# Headers.net
KiCad netlist of a schematic drawn in Altium Designer
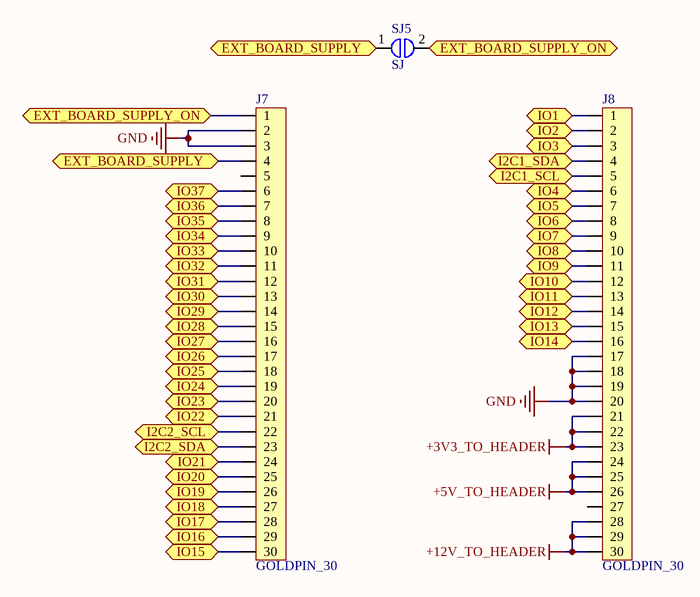
[diagram p0: Headers.SchDoc]

(export (version "E")
  (design (tool "Eeschema 10.0.6"))
  (components
    (comp (ref "J7")
      (value "GOLDPIN_30")
      (footprint "PIN_HEADER_30_MALE")
      (libsource (lib "przem_lib") (part "GOLDPIN_30"))
    )
    (comp (ref "J8")
      (value "GOLDPIN_30")
      (footprint "PIN_HEADER_30_MALE")
      (libsource (lib "przem_lib") (part "GOLDPIN_30"))
    )
    (comp (ref "SJ5") (value "SJ") (footprint "SJ") (libsource (lib "przem_lib") (part "SJ")))
  )
  (nets
    (net (code "1") (name "+3V3_TO_HEADER") (class "Default")
      (node (ref "J8") (pin "21") (pinfunction "21_21") (pintype "passive"))
      (node (ref "J8") (pin "22") (pinfunction "22_22") (pintype "passive"))
      (node (ref "J8") (pin "23") (pinfunction "23_23") (pintype "passive"))
    )
    (net (code "2") (name "+5V_TO_HEADER") (class "Default")
      (node (ref "J8") (pin "24") (pinfunction "24_24") (pintype "passive"))
      (node (ref "J8") (pin "25") (pinfunction "25_25") (pintype "passive"))
      (node (ref "J8") (pin "26") (pinfunction "26_26") (pintype "passive"))
    )
    (net (code "3") (name "+12V_TO_HEADER") (class "Default")
      (node (ref "J8") (pin "28") (pinfunction "28_28") (pintype "passive"))
      (node (ref "J8") (pin "29") (pinfunction "29_29") (pintype "passive"))
      (node (ref "J8") (pin "30") (pinfunction "30_30") (pintype "passive"))
    )
    (net (code "4") (name "/EXT_BOARD_SUPPLY") (class "Default")
      (node (ref "J7") (pin "4") (pinfunction "4_4") (pintype "passive"))
      (node (ref "SJ5") (pin "1") (pinfunction "1_1") (pintype "passive"))
    )
    (net (code "5") (name "/EXT_BOARD_SUPPLY_ON") (class "Default")
      (node (ref "J7") (pin "1") (pinfunction "1_1") (pintype "passive"))
      (node (ref "SJ5") (pin "2") (pinfunction "2_2") (pintype "passive"))
    )
    (net (code "6") (name "/I2C1_SCL") (class "Default")
      (node (ref "J8") (pin "5") (pinfunction "5_5") (pintype "passive"))
    )
    (net (code "7") (name "/I2C1_SDA") (class "Default")
      (node (ref "J8") (pin "4") (pinfunction "4_4") (pintype "passive"))
    )
    (net (code "8") (name "/I2C2_SCL") (class "Default")
      (node (ref "J7") (pin "22") (pinfunction "22_22") (pintype "passive"))
    )
    (net (code "9") (name "/I2C2_SDA") (class "Default")
      (node (ref "J7") (pin "23") (pinfunction "23_23") (pintype "passive"))
    )
    (net (code "10") (name "/IO1") (class "Default")
      (node (ref "J8") (pin "1") (pinfunction "1_1") (pintype "passive"))
    )
    (net (code "11") (name "/IO2") (class "Default")
      (node (ref "J8") (pin "2") (pinfunction "2_2") (pintype "passive"))
    )
    (net (code "12") (name "/IO3") (class "Default")
      (node (ref "J8") (pin "3") (pinfunction "3_3") (pintype "passive"))
    )
    (net (code "13") (name "/IO4") (class "Default")
      (node (ref "J8") (pin "6") (pinfunction "6_6") (pintype "passive"))
    )
    (net (code "14") (name "/IO5") (class "Default")
      (node (ref "J8") (pin "7") (pinfunction "7_7") (pintype "passive"))
    )
    (net (code "15") (name "/IO6") (class "Default")
      (node (ref "J8") (pin "8") (pinfunction "8_8") (pintype "passive"))
    )
    (net (code "16") (name "/IO7") (class "Default")
      (node (ref "J8") (pin "9") (pinfunction "9_9") (pintype "passive"))
    )
    (net (code "17") (name "/IO8") (class "Default")
      (node (ref "J8") (pin "10") (pinfunction "10_10") (pintype "passive"))
    )
    (net (code "18") (name "/IO9") (class "Default")
      (node (ref "J8") (pin "11") (pinfunction "11_11") (pintype "passive"))
    )
    (net (code "19") (name "/IO10") (class "Default")
      (node (ref "J8") (pin "12") (pinfunction "12_12") (pintype "passive"))
    )
    (net (code "20") (name "/IO11") (class "Default")
      (node (ref "J8") (pin "13") (pinfunction "13_13") (pintype "passive"))
    )
    (net (code "21") (name "/IO12") (class "Default")
      (node (ref "J8") (pin "14") (pinfunction "14_14") (pintype "passive"))
    )
    (net (code "22") (name "/IO13") (class "Default")
      (node (ref "J8") (pin "15") (pinfunction "15_15") (pintype "passive"))
    )
    (net (code "23") (name "/IO14") (class "Default")
      (node (ref "J8") (pin "16") (pinfunction "16_16") (pintype "passive"))
    )
    (net (code "24") (name "/IO15") (class "Default")
      (node (ref "J7") (pin "30") (pinfunction "30_30") (pintype "passive"))
    )
    (net (code "25") (name "/IO16") (class "Default")
      (node (ref "J7") (pin "29") (pinfunction "29_29") (pintype "passive"))
    )
    (net (code "26") (name "/IO17") (class "Default")
      (node (ref "J7") (pin "28") (pinfunction "28_28") (pintype "passive"))
    )
    (net (code "27") (name "/IO18") (class "Default")
      (node (ref "J7") (pin "27") (pinfunction "27_27") (pintype "passive"))
    )
    (net (code "28") (name "/IO19") (class "Default")
      (node (ref "J7") (pin "26") (pinfunction "26_26") (pintype "passive"))
    )
    (net (code "29") (name "/IO20") (class "Default")
      (node (ref "J7") (pin "25") (pinfunction "25_25") (pintype "passive"))
    )
    (net (code "30") (name "/IO21") (class "Default")
      (node (ref "J7") (pin "24") (pinfunction "24_24") (pintype "passive"))
    )
    (net (code "31") (name "/IO22") (class "Default")
      (node (ref "J7") (pin "21") (pinfunction "21_21") (pintype "passive"))
    )
    (net (code "32") (name "/IO23") (class "Default")
      (node (ref "J7") (pin "20") (pinfunction "20_20") (pintype "passive"))
    )
    (net (code "33") (name "/IO24") (class "Default")
      (node (ref "J7") (pin "19") (pinfunction "19_19") (pintype "passive"))
    )
    (net (code "34") (name "/IO25") (class "Default")
      (node (ref "J7") (pin "18") (pinfunction "18_18") (pintype "passive"))
    )
    (net (code "35") (name "/IO26") (class "Default")
      (node (ref "J7") (pin "17") (pinfunction "17_17") (pintype "passive"))
    )
    (net (code "36") (name "/IO27") (class "Default")
      (node (ref "J7") (pin "16") (pinfunction "16_16") (pintype "passive"))
    )
    (net (code "37") (name "/IO28") (class "Default")
      (node (ref "J7") (pin "15") (pinfunction "15_15") (pintype "passive"))
    )
    (net (code "38") (name "/IO29") (class "Default")
      (node (ref "J7") (pin "14") (pinfunction "14_14") (pintype "passive"))
    )
    (net (code "39") (name "/IO30") (class "Default")
      (node (ref "J7") (pin "13") (pinfunction "13_13") (pintype "passive"))
    )
    (net (code "40") (name "/IO31") (class "Default")
      (node (ref "J7") (pin "12") (pinfunction "12_12") (pintype "passive"))
    )
    (net (code "41") (name "/IO32") (class "Default")
      (node (ref "J7") (pin "11") (pinfunction "11_11") (pintype "passive"))
    )
    (net (code "42") (name "/IO33") (class "Default")
      (node (ref "J7") (pin "10") (pinfunction "10_10") (pintype "passive"))
    )
    (net (code "43") (name "/IO34") (class "Default")
      (node (ref "J7") (pin "9") (pinfunction "9_9") (pintype "passive"))
    )
    (net (code "44") (name "/IO35") (class "Default")
      (node (ref "J7") (pin "8") (pinfunction "8_8") (pintype "passive"))
    )
    (net (code "45") (name "/IO36") (class "Default")
      (node (ref "J7") (pin "7") (pinfunction "7_7") (pintype "passive"))
    )
    (net (code "46") (name "/IO37") (class "Default")
      (node (ref "J7") (pin "6") (pinfunction "6_6") (pintype "passive"))
    )
    (net (code "47") (name "GND") (class "Default")
      (node (ref "J7") (pin "2") (pinfunction "2_2") (pintype "passive"))
      (node (ref "J7") (pin "3") (pinfunction "3_3") (pintype "passive"))
      (node (ref "J8") (pin "17") (pinfunction "17_17") (pintype "passive"))
      (node (ref "J8") (pin "18") (pinfunction "18_18") (pintype "passive"))
      (node (ref "J8") (pin "19") (pinfunction "19_19") (pintype "passive"))
      (node (ref "J8") (pin "20") (pinfunction "20_20") (pintype "passive"))
    )
    (net (code "48") (name "unconnected-(J7-Pad5)") (class "Default")
      (node (ref "J7") (pin "5") (pinfunction "5_5") (pintype "passive"))
    )
    (net (code "49") (name "unconnected-(J8-Pad27)") (class "Default")
      (node (ref "J8") (pin "27") (pinfunction "27_27") (pintype "passive"))
    )
  )
)
